# PWR_REVE.net
KiCad netlist of a schematic drawn in Altium Designer
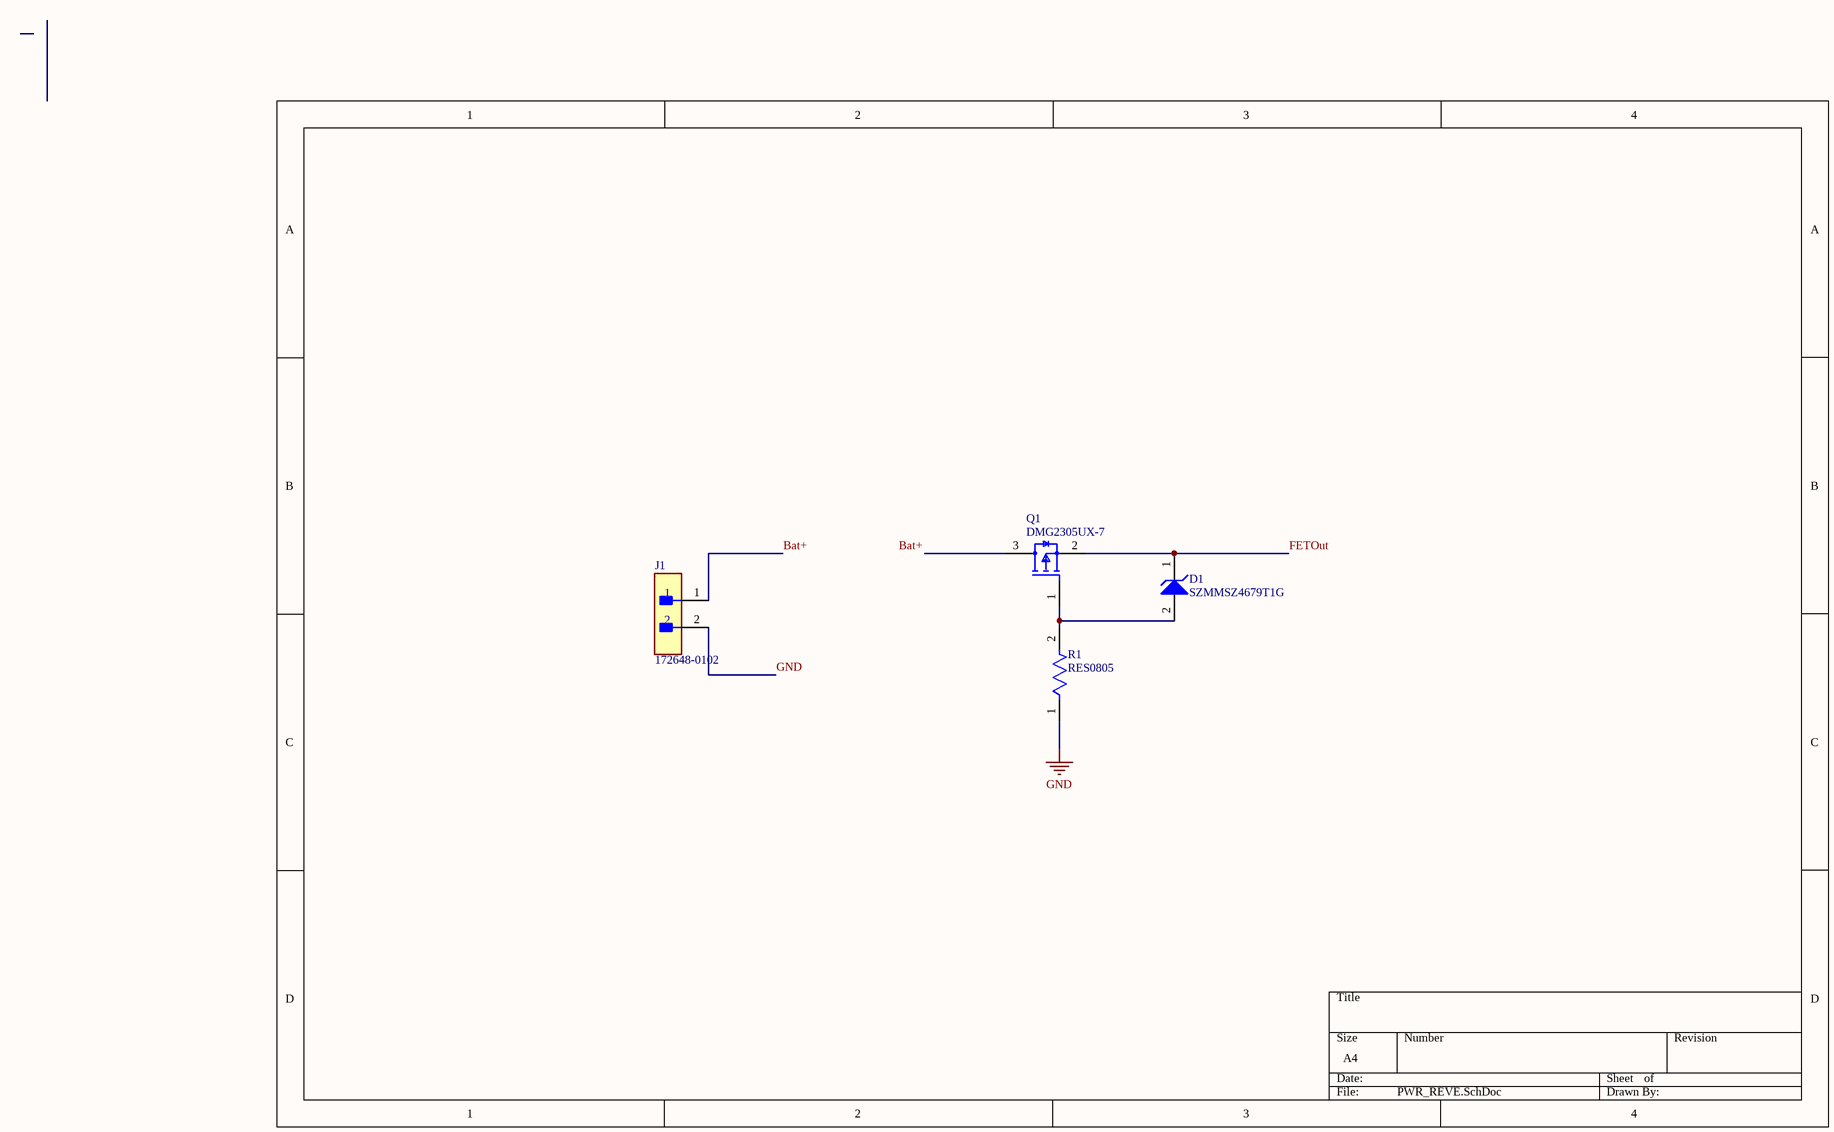
[diagram p0: PWR_REVE.SchDoc]

(export (version "E")
  (design (tool "Eeschema 10.0.6"))
  (components
    (comp (ref "D1")
      (value "SZMMSZ4679T1G")
      (footprint "ONSC-SOD-123-2-425-04_V")
      (description "Zener Voltage Regulator, 500 mW, 2-Pin SOD-123, Pb-Free, Tape and Reel")
      (fields (field (name "MANUFACTURER") "On Semiconductor"))
      (libsource (lib "Altium Content Vault") (part "ONSC-K1A2-2"))
    )
    (comp (ref "J1")
      (value "172648-0102")
      (footprint "FP-172648-0102-MFG")
      (description "CONN HEADER R/A 2POS 4.2MM")
      (libsource (lib "Altium Content Vault") (part "88c1139f9d239099ffebecbe3f7647a"))
    )
    (comp (ref "Q1")
      (value "DMG2305UX-7")
      (footprint "FP-SOT23-IPC_B")
      (description "MOSFET P-CH 20V 4.2A SOT23")
      (libsource (lib "Altium Content Vault") (part "87831b450059b469d4a68f5364f4496"))
    )
    (comp (ref "R1")
      (value "RES0805")
      (footprint "FP-RMCF0805-IPC_C")
      (description "10kΩ")
      (fields (field (name "TOLERANCE") "5%"))
      (libsource (lib "Altium Content Vault") (part "1029c3af85768c4190bb7ad29bc67b5"))
    )
  )
  (nets
    (net (code "1") (name "/Bat+") (class "Default")
      (node (ref "J1") (pin "1") (pinfunction "1_1") (pintype "passive"))
      (node (ref "Q1") (pin "3") (pinfunction "DRAIN_3") (pintype "passive"))
    )
    (net (code "2") (name "/FETOut") (class "Default")
      (node (ref "D1") (pin "1") (pinfunction "K_1") (pintype "passive"))
      (node (ref "Q1") (pin "2") (pinfunction "SOURCE_2") (pintype "passive"))
    )
    (net (code "3") (name "GND") (class "Default")
      (node (ref "J1") (pin "2") (pinfunction "2_2") (pintype "passive"))
      (node (ref "R1") (pin "1") (pinfunction "1_1") (pintype "passive"))
    )
    (net (code "4") (name "Net-(D1-A)") (class "Default")
      (node (ref "D1") (pin "2") (pinfunction "A_2") (pintype "passive"))
      (node (ref "Q1") (pin "1") (pinfunction "GATE_1") (pintype "passive"))
      (node (ref "R1") (pin "2") (pinfunction "2_2") (pintype "passive"))
    )
  )
)
